# RatDistortion.net
KiCad netlist of a schematic drawn in EAGLE
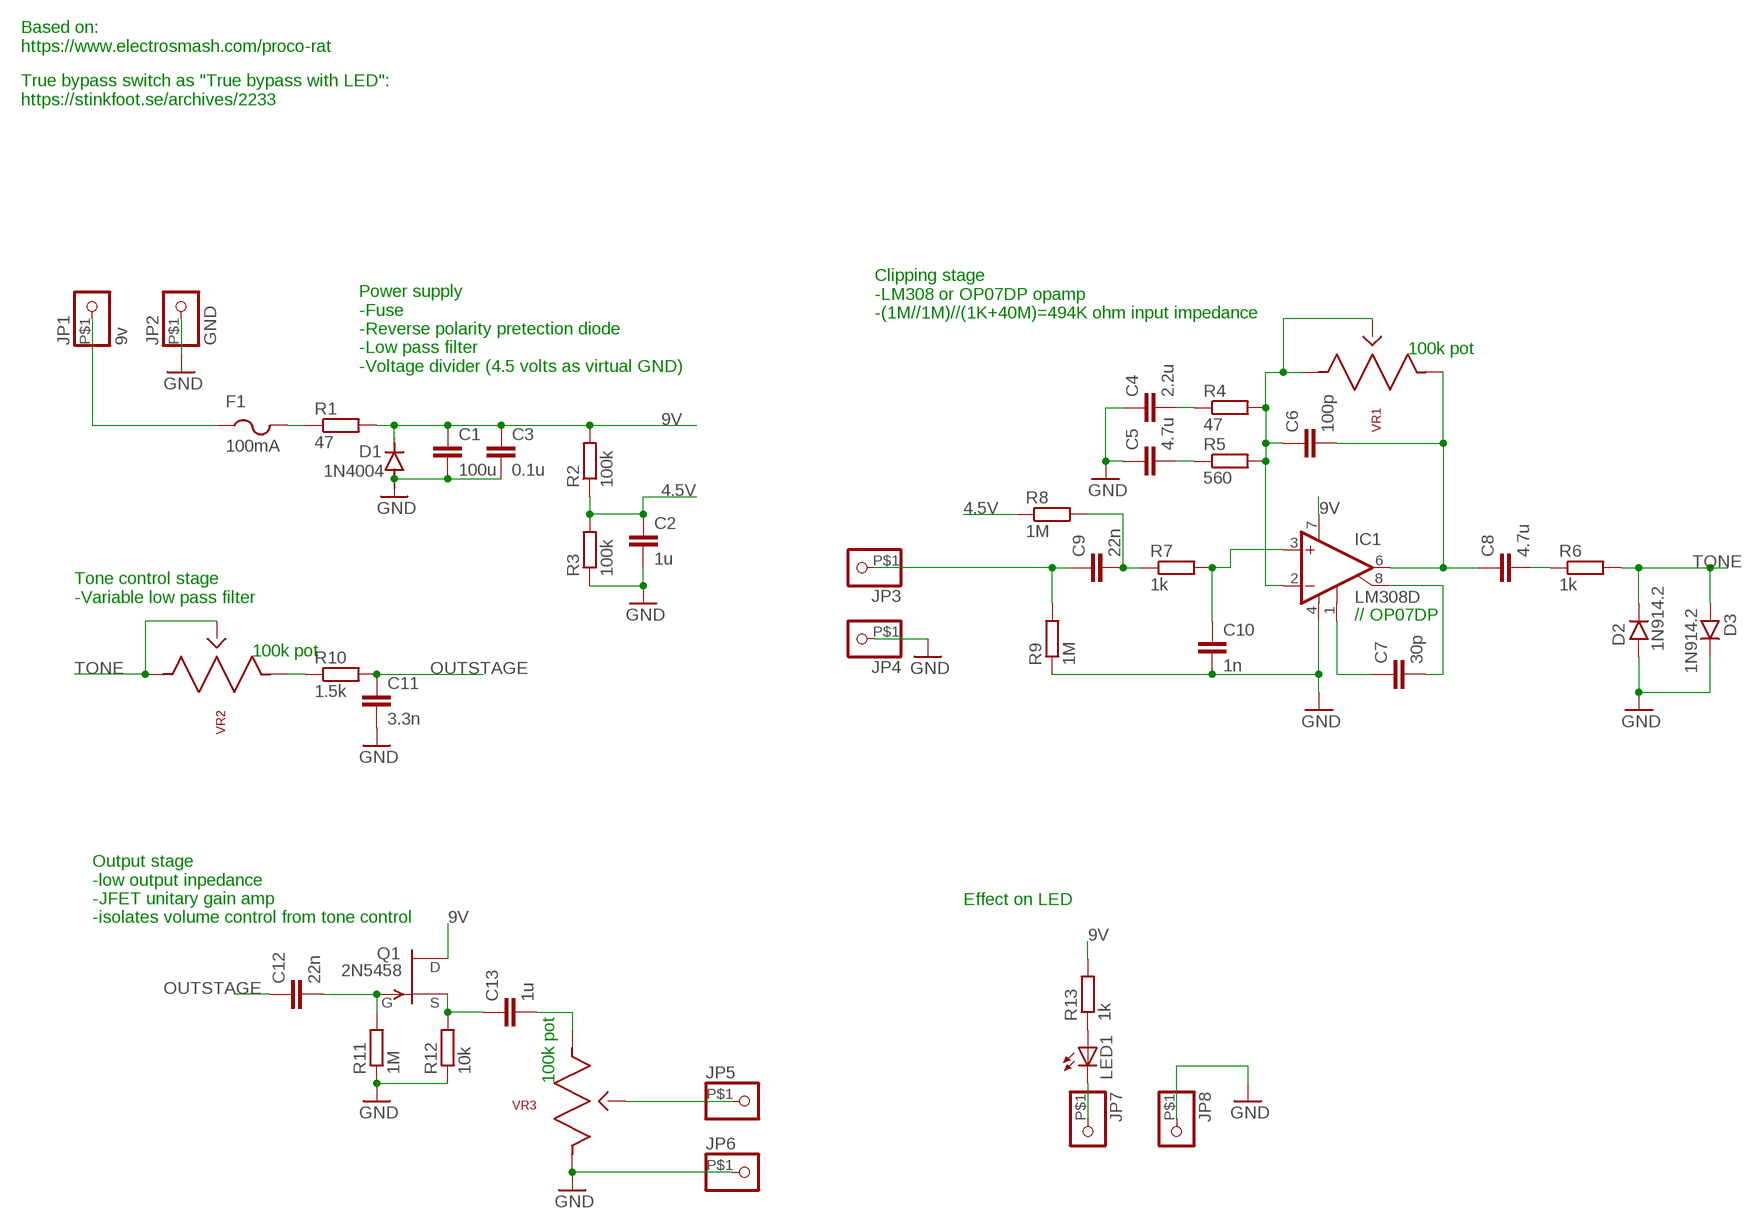
[diagram p0: schematic, sheet 1]

(export (version "E")
  (design (tool "Eeschema 10.0.6"))
  (components
    (comp (ref "C1")
      (value "100u")
      (footprint "eagle-import:C1206")
      (libsource (lib "eagle-import") (part "C-EUC1206"))
    )
    (comp (ref "C2")
      (value "1u")
      (footprint "eagle-import:C1206")
      (libsource (lib "eagle-import") (part "C-EUC1206"))
    )
    (comp (ref "C3")
      (value "0.1u")
      (footprint "eagle-import:C0603")
      (libsource (lib "eagle-import") (part "C-EUC0603"))
    )
    (comp (ref "C4")
      (value "2.2u")
      (footprint "eagle-import:C1206")
      (libsource (lib "eagle-import") (part "C-EUC1206"))
    )
    (comp (ref "C5")
      (value "4.7u")
      (footprint "eagle-import:C1206")
      (libsource (lib "eagle-import") (part "C-EUC1206"))
    )
    (comp (ref "C6")
      (value "100p")
      (footprint "eagle-import:C0603")
      (libsource (lib "eagle-import") (part "C-EUC0603"))
    )
    (comp (ref "C7")
      (value "30p")
      (footprint "eagle-import:C0603")
      (libsource (lib "eagle-import") (part "C-EUC0603"))
    )
    (comp (ref "C8")
      (value "4.7u")
      (footprint "eagle-import:C1206")
      (libsource (lib "eagle-import") (part "C-EUC1206"))
    )
    (comp (ref "C9")
      (value "22n")
      (footprint "eagle-import:C0603")
      (libsource (lib "eagle-import") (part "C-EUC0603"))
    )
    (comp (ref "C10")
      (value "1n")
      (footprint "eagle-import:C0603")
      (libsource (lib "eagle-import") (part "C-EUC0603"))
    )
    (comp (ref "C11")
      (value "3.3n")
      (footprint "eagle-import:C0603")
      (libsource (lib "eagle-import") (part "C-EUC0603"))
    )
    (comp (ref "C12")
      (value "22n")
      (footprint "eagle-import:C0603")
      (libsource (lib "eagle-import") (part "C-EUC0603"))
    )
    (comp (ref "C13")
      (value "1u")
      (footprint "eagle-import:C1206")
      (libsource (lib "eagle-import") (part "C-EUC1206"))
    )
    (comp (ref "D1")
      (value "1N4004")
      (footprint "eagle-import:DO41-10")
      (libsource (lib "eagle-import") (part "1N4004"))
    )
    (comp (ref "D2")
      (value "1N914.2")
      (footprint "eagle-import:DO35-2")
      (fields (field (name "MF") "ON Semiconductor") (field (name "MP") "1N914"))
      (libsource (lib "eagle-import") (part "1N914.2"))
    )
    (comp (ref "D3")
      (value "1N914.2")
      (footprint "eagle-import:DO35-2")
      (fields (field (name "MF") "ON Semiconductor") (field (name "MP") "1N914"))
      (libsource (lib "eagle-import") (part "1N914.2"))
    )
    (comp (ref "F1")
      (value "100mA")
      (footprint "eagle-import:1812")
      (libsource (lib "eagle-import") (part "PTCFUSE-1812"))
    )
    (comp (ref "IC1")
      (value "LM308D")
      (footprint "eagle-import:SO08")
      (libsource (lib "eagle-import") (part "LM308D"))
    )
    (comp (ref "JP1")
      (value "9v")
      (footprint "eagle-import:1X1-BIGPOGO")
      (libsource (lib "eagle-import") (part "PINHD-1X1-BIGPOGO"))
    )
    (comp (ref "JP2")
      (value "GND")
      (footprint "eagle-import:1X1-BIGPOGO")
      (libsource (lib "eagle-import") (part "PINHD-1X1-BIGPOGO"))
    )
    (comp (ref "JP3")
      (value "PINHD-1X1-BIGPOGO")
      (footprint "eagle-import:1X1-BIGPOGO")
      (libsource (lib "eagle-import") (part "PINHD-1X1-BIGPOGO"))
    )
    (comp (ref "JP4")
      (value "PINHD-1X1-BIGPOGO")
      (footprint "eagle-import:1X1-BIGPOGO")
      (libsource (lib "eagle-import") (part "PINHD-1X1-BIGPOGO"))
    )
    (comp (ref "JP5")
      (value "PINHD-1X1-BIGPOGO")
      (footprint "eagle-import:1X1-BIGPOGO")
      (libsource (lib "eagle-import") (part "PINHD-1X1-BIGPOGO"))
    )
    (comp (ref "JP6")
      (value "PINHD-1X1-BIGPOGO")
      (footprint "eagle-import:1X1-BIGPOGO")
      (libsource (lib "eagle-import") (part "PINHD-1X1-BIGPOGO"))
    )
    (comp (ref "JP7")
      (value "PINHD-1X1-BIGPOGO")
      (footprint "eagle-import:1X1-BIGPOGO")
      (libsource (lib "eagle-import") (part "PINHD-1X1-BIGPOGO"))
    )
    (comp (ref "JP8")
      (value "PINHD-1X1-BIGPOGO")
      (footprint "eagle-import:1X1-BIGPOGO")
      (libsource (lib "eagle-import") (part "PINHD-1X1-BIGPOGO"))
    )
    (comp (ref "LED1")
      (value "LED3MM")
      (footprint "eagle-import:LED3MM")
      (libsource (lib "eagle-import") (part "LED3MM"))
    )
    (comp (ref "Q1")
      (value "2N5458")
      (footprint "eagle-import:TO92")
      (libsource (lib "eagle-import") (part "2N5458TO92"))
    )
    (comp (ref "R1")
      (value "47")
      (footprint "eagle-import:R0603")
      (libsource (lib "eagle-import") (part "R-EU_R0603"))
    )
    (comp (ref "R2")
      (value "100k")
      (footprint "eagle-import:R0603")
      (libsource (lib "eagle-import") (part "R-EU_R0603"))
    )
    (comp (ref "R3")
      (value "100k")
      (footprint "eagle-import:R0603")
      (libsource (lib "eagle-import") (part "R-EU_R0603"))
    )
    (comp (ref "R4")
      (value "47")
      (footprint "eagle-import:R0603")
      (libsource (lib "eagle-import") (part "R-EU_R0603"))
    )
    (comp (ref "R5")
      (value "560")
      (footprint "eagle-import:R0603")
      (libsource (lib "eagle-import") (part "R-EU_R0603"))
    )
    (comp (ref "R6")
      (value "1k")
      (footprint "eagle-import:R0603")
      (libsource (lib "eagle-import") (part "R-EU_R0603"))
    )
    (comp (ref "R7")
      (value "1k")
      (footprint "eagle-import:R0603")
      (libsource (lib "eagle-import") (part "R-EU_R0603"))
    )
    (comp (ref "R8")
      (value "1M")
      (footprint "eagle-import:R0603")
      (libsource (lib "eagle-import") (part "R-EU_R0603"))
    )
    (comp (ref "R9")
      (value "1M")
      (footprint "eagle-import:R0603")
      (libsource (lib "eagle-import") (part "R-EU_R0603"))
    )
    (comp (ref "R10")
      (value "1.5k")
      (footprint "eagle-import:R0603")
      (libsource (lib "eagle-import") (part "R-EU_R0603"))
    )
    (comp (ref "R11")
      (value "1M")
      (footprint "eagle-import:R0603")
      (libsource (lib "eagle-import") (part "R-EU_R0603"))
    )
    (comp (ref "R12")
      (value "10k")
      (footprint "eagle-import:R0603")
      (libsource (lib "eagle-import") (part "R-EU_R0603"))
    )
    (comp (ref "R13")
      (value "1k")
      (footprint "eagle-import:R0603")
      (libsource (lib "eagle-import") (part "R-EU_R0603"))
    )
    (comp (ref "VR1")
      (value "PTV09A-4225F-B104")
      (footprint "eagle-import:PTV09")
      (fields (field (name "MF") "Bourns"))
      (libsource (lib "eagle-import") (part "PTV09A-4225F-B104"))
    )
    (comp (ref "VR2")
      (value "PTV09A-4225F-B104")
      (footprint "eagle-import:PTV09")
      (fields (field (name "MF") "Bourns"))
      (libsource (lib "eagle-import") (part "PTV09A-4225F-B104"))
    )
    (comp (ref "VR3")
      (value "PTV09A-4225F-B104")
      (footprint "eagle-import:PTV09")
      (fields (field (name "MF") "Bourns"))
      (libsource (lib "eagle-import") (part "PTV09A-4225F-B104"))
    )
  )
  (nets
    (net (code "1") (name "/4.5V") (class "Default")
      (node (ref "C2") (pin "1") (pinfunction "1_1") (pintype "passive"))
      (node (ref "R2") (pin "1") (pinfunction "1_1") (pintype "passive"))
      (node (ref "R3") (pin "2") (pinfunction "2_2") (pintype "passive"))
      (node (ref "R8") (pin "1") (pinfunction "1_1") (pintype "passive"))
    )
    (net (code "2") (name "/9V") (class "Default")
      (node (ref "C1") (pin "1") (pinfunction "1_1") (pintype "passive"))
      (node (ref "C3") (pin "1") (pinfunction "1_1") (pintype "passive"))
      (node (ref "D1") (pin "C") (pinfunction "C_C") (pintype "passive"))
      (node (ref "IC1") (pin "7") (pinfunction "V+_7") (pintype "power_in"))
      (node (ref "Q1") (pin "3") (pinfunction "D_3") (pintype "passive"))
      (node (ref "R1") (pin "2") (pinfunction "2_2") (pintype "passive"))
      (node (ref "R13") (pin "2") (pinfunction "2_2") (pintype "passive"))
      (node (ref "R2") (pin "2") (pinfunction "2_2") (pintype "passive"))
    )
    (net (code "3") (name "/OUTSTAGE") (class "Default")
      (node (ref "C11") (pin "1") (pinfunction "1_1") (pintype "passive"))
      (node (ref "C12") (pin "1") (pinfunction "1_1") (pintype "passive"))
      (node (ref "R10") (pin "2") (pinfunction "2_2") (pintype "passive"))
    )
    (net (code "4") (name "/TONE") (class "Default")
      (node (ref "D2") (pin "C") (pinfunction "C_C") (pintype "passive"))
      (node (ref "D3") (pin "A") (pinfunction "A_A") (pintype "passive"))
      (node (ref "R6") (pin "2") (pinfunction "2_2") (pintype "passive"))
      (node (ref "VR2") (pin "2") (pinfunction "2_2") (pintype "bidirectional"))
      (node (ref "VR2") (pin "3") (pinfunction "3_3") (pintype "bidirectional"))
    )
    (net (code "5") (name "GND") (class "Default")
      (node (ref "C1") (pin "2") (pinfunction "2_2") (pintype "passive"))
      (node (ref "C10") (pin "2") (pinfunction "2_2") (pintype "passive"))
      (node (ref "C11") (pin "2") (pinfunction "2_2") (pintype "passive"))
      (node (ref "C2") (pin "2") (pinfunction "2_2") (pintype "passive"))
      (node (ref "C3") (pin "2") (pinfunction "2_2") (pintype "passive"))
      (node (ref "C4") (pin "1") (pinfunction "1_1") (pintype "passive"))
      (node (ref "C5") (pin "1") (pinfunction "1_1") (pintype "passive"))
      (node (ref "D1") (pin "A") (pinfunction "A_A") (pintype "passive"))
      (node (ref "D2") (pin "A") (pinfunction "A_A") (pintype "passive"))
      (node (ref "D3") (pin "C") (pinfunction "C_C") (pintype "passive"))
      (node (ref "IC1") (pin "4") (pinfunction "V-_4") (pintype "power_in"))
      (node (ref "JP2") (pin "P$1") (pinfunction "1_P$1") (pintype "passive"))
      (node (ref "JP4") (pin "P$1") (pinfunction "1_P$1") (pintype "passive"))
      (node (ref "JP6") (pin "P$1") (pinfunction "1_P$1") (pintype "passive"))
      (node (ref "JP8") (pin "P$1") (pinfunction "1_P$1") (pintype "passive"))
      (node (ref "R11") (pin "1") (pinfunction "1_1") (pintype "passive"))
      (node (ref "R12") (pin "1") (pinfunction "1_1") (pintype "passive"))
      (node (ref "R3") (pin "1") (pinfunction "1_1") (pintype "passive"))
      (node (ref "R9") (pin "1") (pinfunction "1_1") (pintype "passive"))
      (node (ref "VR3") (pin "1") (pinfunction "1_1") (pintype "bidirectional"))
    )
    (net (code "6") (name "Net-(C4-Pad2)") (class "Default")
      (node (ref "C4") (pin "2") (pinfunction "2_2") (pintype "passive"))
      (node (ref "R4") (pin "1") (pinfunction "1_1") (pintype "passive"))
    )
    (net (code "7") (name "Net-(C5-Pad2)") (class "Default")
      (node (ref "C5") (pin "2") (pinfunction "2_2") (pintype "passive"))
      (node (ref "R5") (pin "1") (pinfunction "1_1") (pintype "passive"))
    )
    (net (code "8") (name "Net-(C8-Pad2)") (class "Default")
      (node (ref "C8") (pin "2") (pinfunction "2_2") (pintype "passive"))
      (node (ref "R6") (pin "1") (pinfunction "1_1") (pintype "passive"))
    )
    (net (code "9") (name "Net-(C9-Pad2)") (class "Default")
      (node (ref "C9") (pin "2") (pinfunction "2_2") (pintype "passive"))
      (node (ref "R7") (pin "1") (pinfunction "1_1") (pintype "passive"))
      (node (ref "R8") (pin "2") (pinfunction "2_2") (pintype "passive"))
    )
    (net (code "10") (name "Net-(C13-Pad2)") (class "Default")
      (node (ref "C13") (pin "2") (pinfunction "2_2") (pintype "passive"))
      (node (ref "VR3") (pin "3") (pinfunction "3_3") (pintype "bidirectional"))
    )
    (net (code "11") (name "Net-(F1-Pad2)") (class "Default")
      (node (ref "F1") (pin "2") (pinfunction "2_2") (pintype "passive"))
      (node (ref "R1") (pin "1") (pinfunction "1_1") (pintype "passive"))
    )
    (net (code "12") (name "Net-(IC1-+IN)") (class "Default")
      (node (ref "C10") (pin "1") (pinfunction "1_1") (pintype "passive"))
      (node (ref "IC1") (pin "3") (pinfunction "+IN_3") (pintype "input"))
      (node (ref "R7") (pin "2") (pinfunction "2_2") (pintype "passive"))
    )
    (net (code "13") (name "Net-(IC1--IN)") (class "Default")
      (node (ref "C6") (pin "1") (pinfunction "1_1") (pintype "passive"))
      (node (ref "IC1") (pin "2") (pinfunction "-IN_2") (pintype "input"))
      (node (ref "R4") (pin "2") (pinfunction "2_2") (pintype "passive"))
      (node (ref "R5") (pin "2") (pinfunction "2_2") (pintype "passive"))
      (node (ref "VR1") (pin "2") (pinfunction "2_2") (pintype "bidirectional"))
      (node (ref "VR1") (pin "3") (pinfunction "3_3") (pintype "bidirectional"))
    )
    (net (code "14") (name "Net-(IC1-CMP1)") (class "Default")
      (node (ref "C7") (pin "1") (pinfunction "1_1") (pintype "passive"))
      (node (ref "IC1") (pin "1") (pinfunction "CMP1_1") (pintype "passive"))
    )
    (net (code "15") (name "Net-(IC1-CMP2)") (class "Default")
      (node (ref "C7") (pin "2") (pinfunction "2_2") (pintype "passive"))
      (node (ref "IC1") (pin "8") (pinfunction "CMP2_8") (pintype "passive"))
    )
    (net (code "16") (name "Net-(IC1-OUT)") (class "Default")
      (node (ref "C6") (pin "2") (pinfunction "2_2") (pintype "passive"))
      (node (ref "C8") (pin "1") (pinfunction "1_1") (pintype "passive"))
      (node (ref "IC1") (pin "6") (pinfunction "OUT_6") (pintype "output"))
      (node (ref "VR1") (pin "1") (pinfunction "1_1") (pintype "bidirectional"))
    )
    (net (code "17") (name "Net-(JP1-1)") (class "Default")
      (node (ref "F1") (pin "1") (pinfunction "1_1") (pintype "passive"))
      (node (ref "JP1") (pin "P$1") (pinfunction "1_P$1") (pintype "passive"))
    )
    (net (code "18") (name "Net-(JP3-1)") (class "Default")
      (node (ref "C9") (pin "1") (pinfunction "1_1") (pintype "passive"))
      (node (ref "JP3") (pin "P$1") (pinfunction "1_P$1") (pintype "passive"))
      (node (ref "R9") (pin "2") (pinfunction "2_2") (pintype "passive"))
    )
    (net (code "19") (name "Net-(JP5-1)") (class "Default")
      (node (ref "JP5") (pin "P$1") (pinfunction "1_P$1") (pintype "passive"))
      (node (ref "VR3") (pin "2") (pinfunction "2_2") (pintype "bidirectional"))
    )
    (net (code "20") (name "Net-(JP7-1)") (class "Default")
      (node (ref "JP7") (pin "P$1") (pinfunction "1_P$1") (pintype "passive"))
      (node (ref "LED1") (pin "K") (pinfunction "C_K") (pintype "passive"))
    )
    (net (code "21") (name "Net-(LED1-PadA)") (class "Default")
      (node (ref "LED1") (pin "A") (pinfunction "A_A") (pintype "passive"))
      (node (ref "R13") (pin "1") (pinfunction "1_1") (pintype "passive"))
    )
    (net (code "22") (name "Net-(Q1-G)") (class "Default")
      (node (ref "C12") (pin "2") (pinfunction "2_2") (pintype "passive"))
      (node (ref "Q1") (pin "1") (pinfunction "G_1") (pintype "passive"))
      (node (ref "R11") (pin "2") (pinfunction "2_2") (pintype "passive"))
    )
    (net (code "23") (name "Net-(Q1-S)") (class "Default")
      (node (ref "C13") (pin "1") (pinfunction "1_1") (pintype "passive"))
      (node (ref "Q1") (pin "2") (pinfunction "S_2") (pintype "passive"))
      (node (ref "R12") (pin "2") (pinfunction "2_2") (pintype "passive"))
    )
    (net (code "24") (name "Net-(R10-Pad1)") (class "Default")
      (node (ref "R10") (pin "1") (pinfunction "1_1") (pintype "passive"))
      (node (ref "VR2") (pin "1") (pinfunction "1_1") (pintype "bidirectional"))
    )
  )
)
